# nrf52840_test_board.net
KiCad netlist of a schematic drawn in EasyEDA Pro
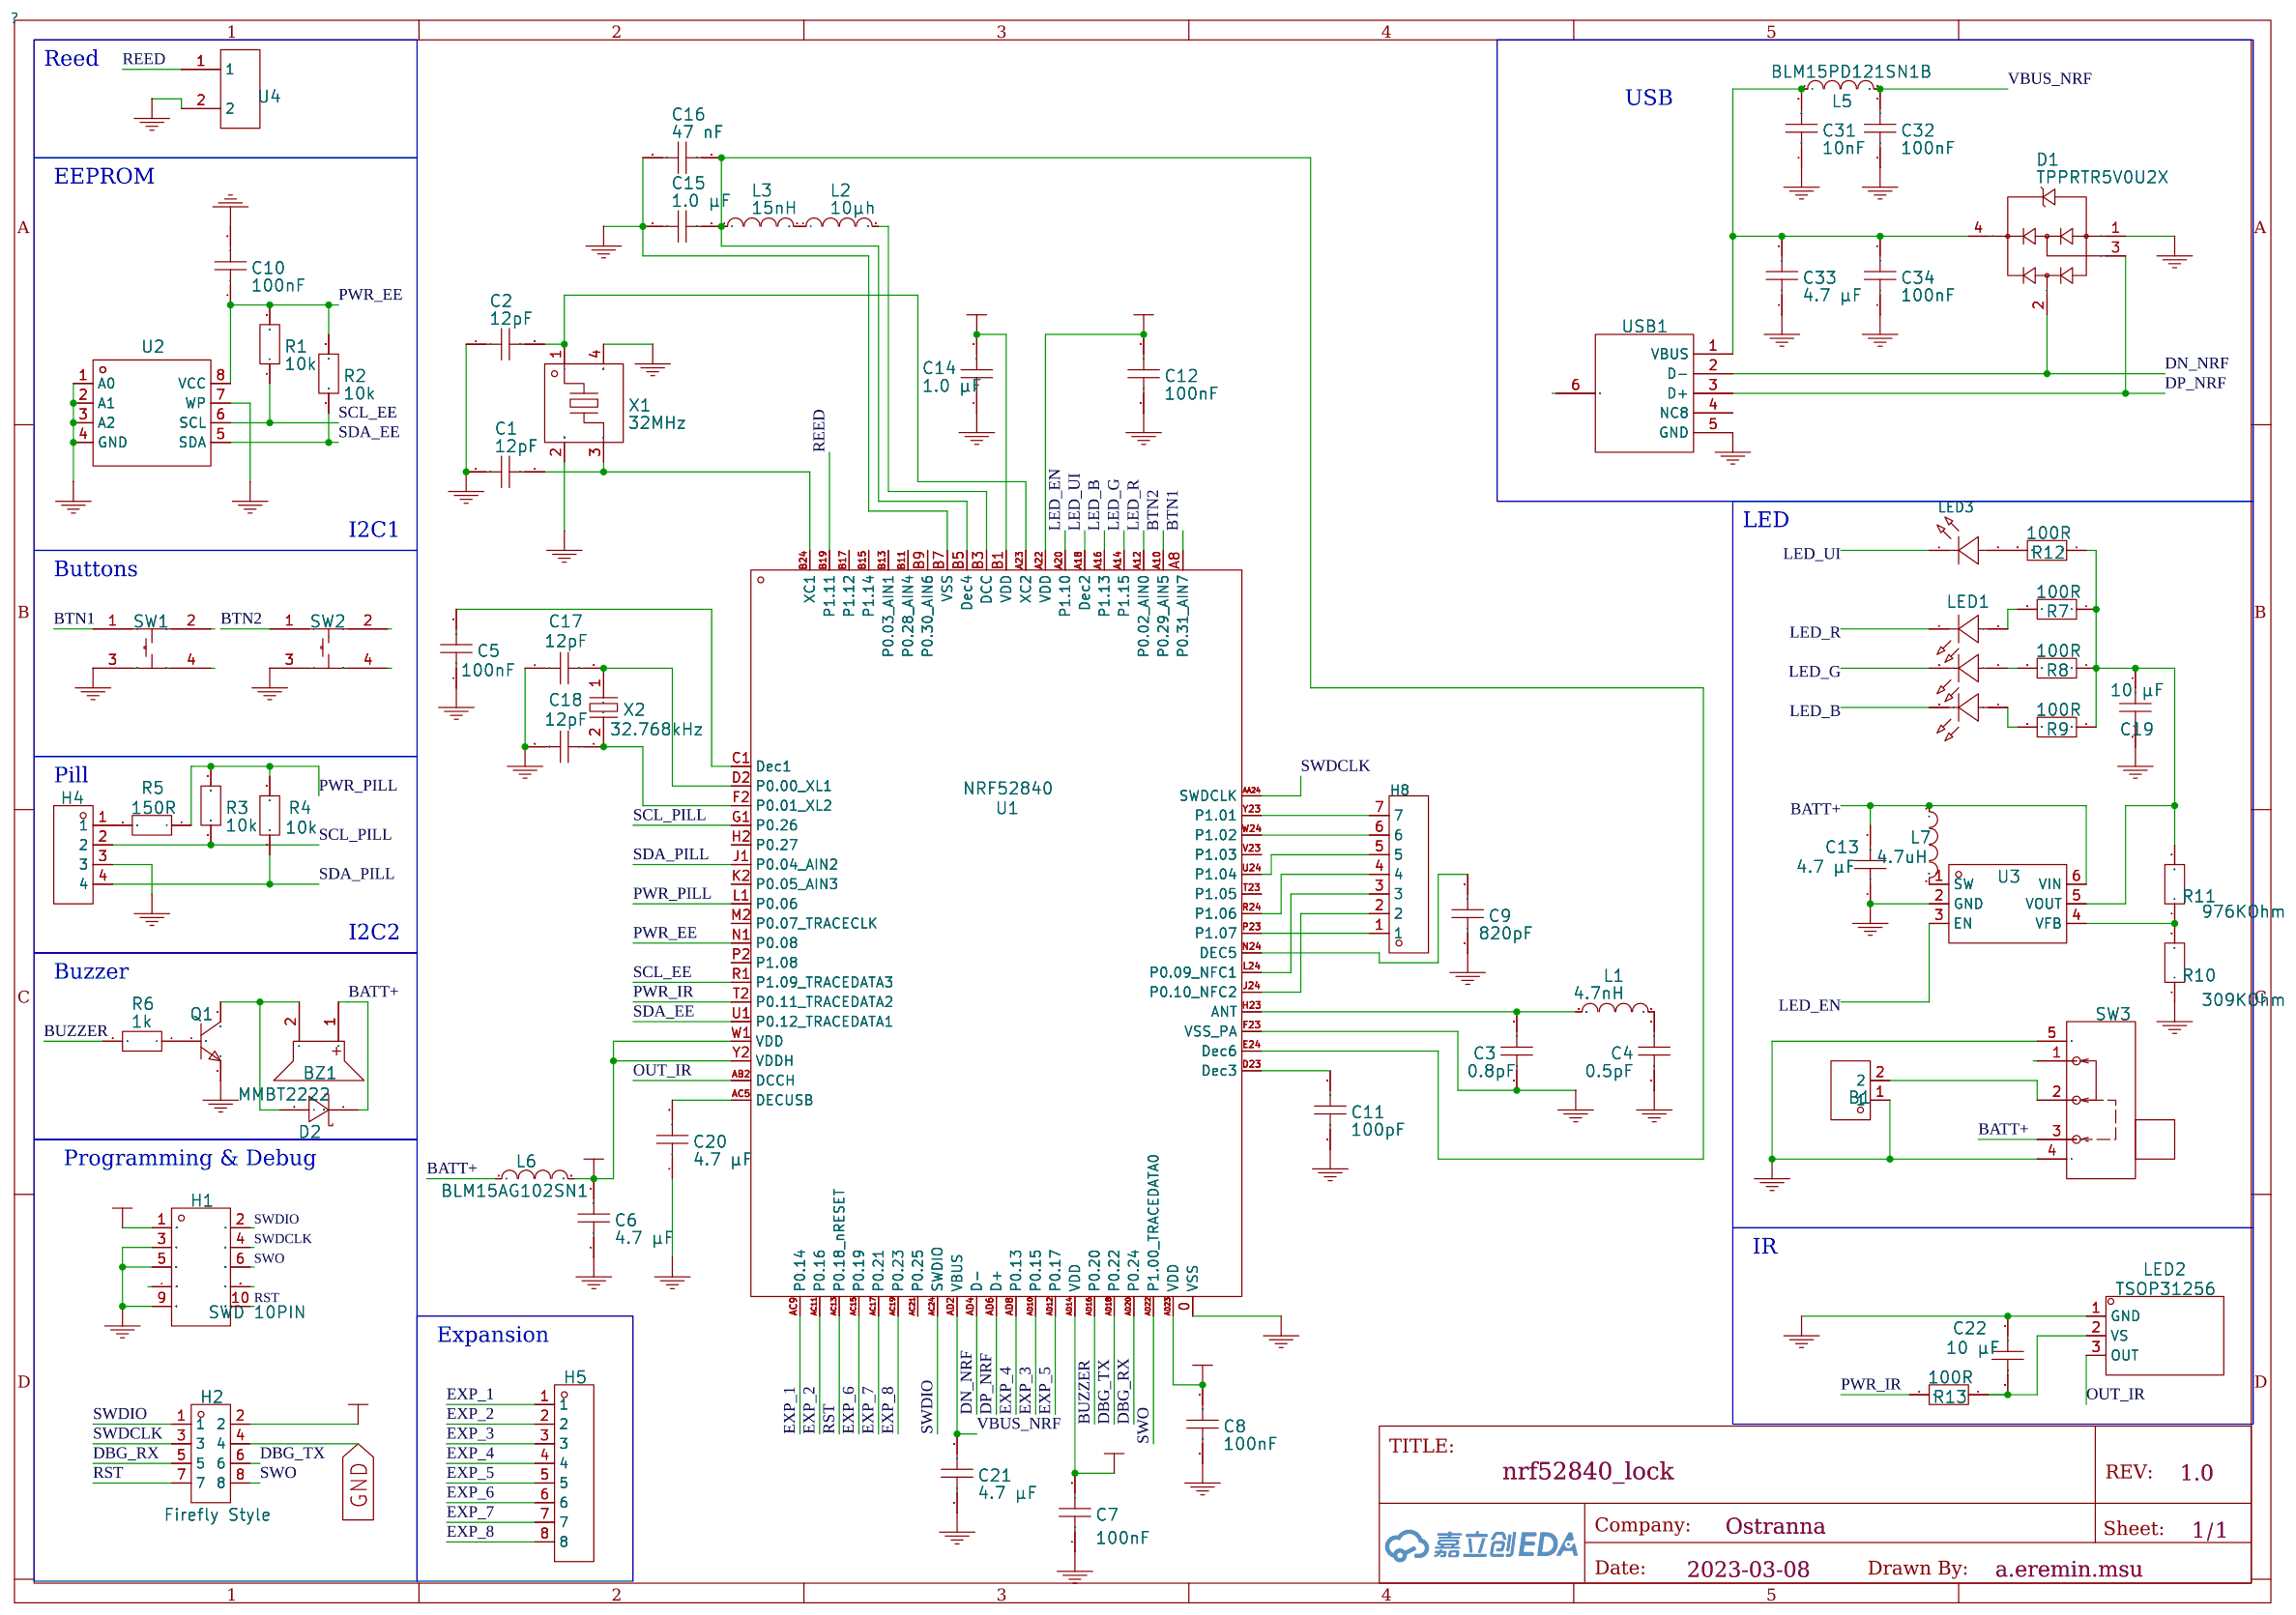
[diagram p0: schematic sheet]

(export (version "E")
  (design (tool "Eeschema 10.0.6"))
  (components
    (comp (ref "B1")
      (value "MF200V-11-02P")
      (footprint "easyedapro:HDR-TH_2P-P2.00-V-F-3")
      (fields (field (name "Manufacturer") "XFCN(兴飞)"))
      (libsource (lib "easyedapro") (part "MF200V-11-02P"))
    )
    (comp (ref "BZ1")
      (value "QMB-09B-03")
      (footprint "easyedapro:BUZ-TH_BD9.0-P4.00-D0.6-FD")
      (fields (field (name "Manufacturer") "华能"))
      (libsource (lib "easyedapro") (part "QMB-09B-03"))
    )
    (comp (ref "C1")
      (value "12pF")
      (footprint "easyedapro:C0402")
      (fields (field (name "Manufacturer Part") "0402CG120J500NT") (field (name "Manufacturer") "FH(风华)"))
      (libsource (lib "easyedapro") (part "12pF"))
    )
    (comp (ref "C2")
      (value "12pF")
      (footprint "easyedapro:C0402")
      (fields (field (name "Manufacturer Part") "0402CG120J500NT") (field (name "Manufacturer") "FH(风华)"))
      (libsource (lib "easyedapro") (part "12pF"))
    )
    (comp (ref "C3")
      (value "0.8pF")
      (footprint "easyedapro:C0402")
      (fields
        (field (name "Manufacturer Part") "GJM1555C1HR80WB01D")
        (field (name "Manufacturer") "muRata(村田)")
      )
      (libsource (lib "easyedapro") (part "0.8pF"))
    )
    (comp (ref "C4")
      (value "0.5pF")
      (footprint "easyedapro:C0402")
      (fields (field (name "Manufacturer Part") "0402CG0R5B500NT") (field (name "Manufacturer") "FH(风华)"))
      (libsource (lib "easyedapro") (part "0.5pF"))
    )
    (comp (ref "C5")
      (value "100nF")
      (footprint "easyedapro:C0402")
      (fields
        (field (name "Manufacturer Part") "GRM155R71C104KA88D")
        (field (name "Manufacturer") "muRata(村田)")
      )
      (libsource (lib "easyedapro") (part "100nF"))
    )
    (comp (ref "C6")
      (value "4.7 µF")
      (footprint "easyedapro:C0603")
      (fields
        (field (name "Manufacturer Part") "GRM188R60J475KE19D")
        (field (name "Manufacturer") "muRata(村田)")
      )
      (libsource (lib "easyedapro") (part "4.7 µF"))
    )
    (comp (ref "C7")
      (value "100nF")
      (footprint "easyedapro:C0402")
      (fields
        (field (name "Manufacturer Part") "GRM155R71C104KA88D")
        (field (name "Manufacturer") "muRata(村田)")
      )
      (libsource (lib "easyedapro") (part "100nF"))
    )
    (comp (ref "C8")
      (value "100nF")
      (footprint "easyedapro:C0402")
      (fields
        (field (name "Manufacturer Part") "GRM155R71C104KA88D")
        (field (name "Manufacturer") "muRata(村田)")
      )
      (libsource (lib "easyedapro") (part "100nF"))
    )
    (comp (ref "C9")
      (value "820pF")
      (footprint "easyedapro:C0402")
      (fields
        (field (name "Manufacturer Part") "GCM1555C1H821JA16D")
        (field (name "Manufacturer") "muRata(村田)")
      )
      (libsource (lib "easyedapro") (part "820pF"))
    )
    (comp (ref "C10")
      (value "100nF")
      (footprint "easyedapro:C0402")
      (fields
        (field (name "Manufacturer Part") "GRM155R71C104KA88D")
        (field (name "Manufacturer") "muRata(村田)")
      )
      (libsource (lib "easyedapro") (part "100nF"))
    )
    (comp (ref "C11")
      (value "100pF")
      (footprint "easyedapro:C0402")
      (fields
        (field (name "Manufacturer Part") "GCM1555C1H101JA16D")
        (field (name "Manufacturer") "muRata(村田)")
      )
      (libsource (lib "easyedapro") (part "100pF"))
    )
    (comp (ref "C12")
      (value "100nF")
      (footprint "easyedapro:C0402")
      (fields
        (field (name "Manufacturer Part") "GRM155R71C104KA88D")
        (field (name "Manufacturer") "muRata(村田)")
      )
      (libsource (lib "easyedapro") (part "100nF"))
    )
    (comp (ref "C13")
      (value "4.7 µF")
      (footprint "easyedapro:C0603")
      (fields
        (field (name "Manufacturer Part") "GRM188R60J475KE19D")
        (field (name "Manufacturer") "muRata(村田)")
      )
      (libsource (lib "easyedapro") (part "4.7 µF"))
    )
    (comp (ref "C14")
      (value "1.0 µF")
      (footprint "easyedapro:C0603")
      (fields
        (field (name "Manufacturer Part") "CL10A105KB8NNNC")
        (field (name "Manufacturer") "SAMSUNG(三星)")
      )
      (libsource (lib "easyedapro") (part "1.0 µF"))
    )
    (comp (ref "C15")
      (value "1.0 µF")
      (footprint "easyedapro:C0603")
      (fields
        (field (name "Manufacturer Part") "CL10A105KB8NNNC")
        (field (name "Manufacturer") "SAMSUNG(三星)")
      )
      (libsource (lib "easyedapro") (part "1.0 µF"))
    )
    (comp (ref "C16")
      (value "47 nF")
      (footprint "easyedapro:C0402")
      (fields (field (name "Manufacturer Part") "0402B473K250CT") (field (name "Manufacturer") "Walsin(华新科)"))
      (libsource (lib "easyedapro") (part "47 nF"))
    )
    (comp (ref "C17")
      (value "12pF")
      (footprint "easyedapro:C0402")
      (fields (field (name "Manufacturer Part") "0402CG120J500NT") (field (name "Manufacturer") "FH(风华)"))
      (libsource (lib "easyedapro") (part "12pF"))
    )
    (comp (ref "C18")
      (value "12pF")
      (footprint "easyedapro:C0402")
      (fields (field (name "Manufacturer Part") "0402CG120J500NT") (field (name "Manufacturer") "FH(风华)"))
      (libsource (lib "easyedapro") (part "12pF"))
    )
    (comp (ref "C19")
      (value "10 µF")
      (footprint "easyedapro:C0603")
      (fields
        (field (name "Manufacturer Part") "CL10A105KB8NNNC")
        (field (name "Manufacturer") "SAMSUNG(三星)")
      )
      (libsource (lib "easyedapro") (part "1.0 µF"))
    )
    (comp (ref "C20")
      (value "4.7 µF")
      (footprint "easyedapro:C0603")
      (fields
        (field (name "Manufacturer Part") "GRM188R60J475KE19D")
        (field (name "Manufacturer") "muRata(村田)")
      )
      (libsource (lib "easyedapro") (part "4.7 µF"))
    )
    (comp (ref "C21")
      (value "4.7 µF")
      (footprint "easyedapro:C0603")
      (fields
        (field (name "Manufacturer Part") "GRM188R60J475KE19D")
        (field (name "Manufacturer") "muRata(村田)")
      )
      (libsource (lib "easyedapro") (part "4.7 µF"))
    )
    (comp (ref "C22")
      (value "10 µF")
      (footprint "easyedapro:C0603")
      (fields
        (field (name "Manufacturer Part") "CL10A105KB8NNNC")
        (field (name "Manufacturer") "SAMSUNG(三星)")
      )
      (libsource (lib "easyedapro") (part "1.0 µF"))
    )
    (comp (ref "C31")
      (value "10nF")
      (footprint "easyedapro:C0402")
      (fields (field (name "Manufacturer Part") "0402B103J160NT") (field (name "Manufacturer") "FH(风华)"))
      (libsource (lib "easyedapro") (part "10nF"))
    )
    (comp (ref "C32")
      (value "100nF")
      (footprint "easyedapro:C0402")
      (fields
        (field (name "Manufacturer Part") "GRM155R71C104KA88D")
        (field (name "Manufacturer") "muRata(村田)")
      )
      (libsource (lib "easyedapro") (part "100nF"))
    )
    (comp (ref "C33")
      (value "4.7 µF")
      (footprint "easyedapro:C0603")
      (fields
        (field (name "Manufacturer Part") "GRM188R60J475KE19D")
        (field (name "Manufacturer") "muRata(村田)")
      )
      (libsource (lib "easyedapro") (part "4.7 µF"))
    )
    (comp (ref "C34")
      (value "100nF")
      (footprint "easyedapro:C0402")
      (fields
        (field (name "Manufacturer Part") "GRM155R71C104KA88D")
        (field (name "Manufacturer") "muRata(村田)")
      )
      (libsource (lib "easyedapro") (part "100nF"))
    )
    (comp (ref "D1")
      (value "TPPRTR5V0U2X")
      (footprint "easyedapro:SOT-143_L2.9-W1.3-P1.92-LS2.3-BR")
      (fields (field (name "Manufacturer") "TECH PUBLIC(台舟)"))
      (libsource (lib "easyedapro") (part "TPPRTR5V0U2X"))
    )
    (comp (ref "D2")
      (value "BAT54WS_C397611")
      (footprint "easyedapro:SOD-323_L1.8-W1.3-LS2.5-RD")
      (fields (field (name "Manufacturer Part") "BAT54WS") (field (name "Manufacturer") "AnBon(安邦)"))
      (libsource (lib "easyedapro") (part "BAT54WS_C397611"))
    )
    (comp (ref "H1")
      (value "SWD 10PIN")
      (footprint "easyedapro:HDR-SMD_10P-P1.27-V-M-R2-C5-LS5.5")
      (fields
        (field (name "Manufacturer Part") "KH-1.27PH180-2X5P-L7.2-SMT")
        (field (name "Manufacturer") "kinghelm(金航标)")
      )
      (libsource (lib "easyedapro") (part "SWD 10PIN"))
    )
    (comp (ref "H2")
      (value "Firefly Style")
      (footprint "easyedapro:HDR-TH_8P-P2.54-V-M-R2-C4-S2.54")
      (fields
        (field (name "Manufacturer Part") "DZ254R-22-08-63")
        (field (name "Manufacturer") "DEALON(德艺隆)")
      )
      (libsource (lib "easyedapro") (part "Firefly Style"))
    )
    (comp (ref "H4")
      (value "DW254W-11-04-85")
      (footprint "easyedapro:HDR-TH_4P-P2.54-H-F-W10.3-N")
      (fields (field (name "Manufacturer") "DEALON(德艺隆)"))
      (libsource (lib "easyedapro") (part "DW254W-11-04-85"))
    )
    (comp (ref "H5")
      (value "DW254W-11-08-85")
      (footprint "easyedapro:HDR-TH_8P-P2.54-H-F-W10.3-N")
      (fields (field (name "Manufacturer") "DEALON(德艺隆)"))
      (libsource (lib "easyedapro") (part "DW254W-11-08-85"))
    )
    (comp (ref "H8")
      (value "PZ254R-11-07P")
      (footprint "easyedapro:HDR-TH_7P-P2.54-H-M-W10.4")
      (fields (field (name "Manufacturer") "XFCN(兴飞)"))
      (libsource (lib "easyedapro") (part "PZ254R-11-07P"))
    )
    (comp (ref "L1")
      (value "4.7nH")
      (footprint "easyedapro:C0402")
      (fields (field (name "Manufacturer Part") "LQP15MN4N7B02D") (field (name "Manufacturer") "muRata(村田)"))
      (libsource (lib "easyedapro") (part "4.7nH"))
    )
    (comp (ref "L2")
      (value "10µh")
      (footprint "easyedapro:L0603")
      (fields
        (field (name "Manufacturer Part") "LBMF1608T100K")
        (field (name "Manufacturer") "TAIYO YUDEN(太诱)")
      )
      (libsource (lib "easyedapro") (part "10µh"))
    )
    (comp (ref "L3")
      (value "15nH")
      (footprint "easyedapro:C0402")
      (fields
        (field (name "Manufacturer Part") "CS0402-15NH-S")
        (field (name "Manufacturer") "chilisin(奇力新)")
      )
      (libsource (lib "easyedapro") (part "15nH"))
    )
    (comp (ref "L5")
      (value "BLM15PD121SN1B")
      (footprint "easyedapro:L0402")
      (fields (field (name "Manufacturer Part") "BLM15PD121SN1D") (field (name "Manufacturer") "muRata(村田)"))
      (libsource (lib "easyedapro") (part "BLM15PD121SN1B"))
    )
    (comp (ref "L6")
      (value "BLM15AG102SN1")
      (footprint "easyedapro:L0402")
      (fields (field (name "Manufacturer Part") "BLM15AG102SN1D") (field (name "Manufacturer") "muRata(村田)"))
      (libsource (lib "easyedapro") (part "BLM15AG102SN1"))
    )
    (comp (ref "L7")
      (value "4.7uH")
      (footprint "easyedapro:L0603")
      (fields
        (field (name "Manufacturer Part") "CPY160808T-4R7M-NP")
        (field (name "Manufacturer") "chilisin(奇力新)")
      )
      (libsource (lib "easyedapro") (part "4.7uH"))
    )
    (comp (ref "LED1")
      (value "TC5050RGBF08-3CJH-AF53A")
      (footprint "easyedapro:LED-SMD_6P-L5.0-W5.0-TL_TC5050RGBF08")
      (fields (field (name "Manufacturer") "TCWIN(天成)"))
      (libsource (lib "easyedapro") (part "TC5050RGBF08-3CJH-AF53A"))
    )
    (comp (ref "LED2")
      (value "TSOP31256")
      (footprint "easyedapro:SENSOR-TH_TSOP31256")
      (fields (field (name "Manufacturer") "VISHAY(威世)"))
      (libsource (lib "easyedapro") (part "TSOP31256"))
    )
    (comp (ref "LED3")
      (value "LTST-T680TGWT")
      (footprint "easyedapro:LED-SMD_L3.2-W2.8-LS3.5-RD_GREEN")
      (fields (field (name "Manufacturer") "LITEON(光宝)"))
      (libsource (lib "easyedapro") (part "LTST-T680TGWT"))
    )
    (comp (ref "Q1")
      (value "MMBT2222")
      (footprint "easyedapro:SOT-23-3_L2.9-W1.4-P1.91-LS2.6-BR")
      (fields (field (name "Manufacturer") "YONGYUTAI(永裕泰)"))
      (libsource (lib "easyedapro") (part "MMBT2222"))
    )
    (comp (ref "R1")
      (value "10k")
      (footprint "easyedapro:R0603")
      (fields
        (field (name "Manufacturer Part") "0603WAF1002T5E")
        (field (name "Manufacturer") "UNI-ROYAL(厚声)")
      )
      (libsource (lib "easyedapro") (part "10k"))
    )
    (comp (ref "R2")
      (value "10k")
      (footprint "easyedapro:R0603")
      (fields
        (field (name "Manufacturer Part") "0603WAF1002T5E")
        (field (name "Manufacturer") "UNI-ROYAL(厚声)")
      )
      (libsource (lib "easyedapro") (part "10k"))
    )
    (comp (ref "R3")
      (value "10k")
      (footprint "easyedapro:R0603")
      (fields
        (field (name "Manufacturer Part") "0603WAF1002T5E")
        (field (name "Manufacturer") "UNI-ROYAL(厚声)")
      )
      (libsource (lib "easyedapro") (part "10k"))
    )
    (comp (ref "R4")
      (value "10k")
      (footprint "easyedapro:R0603")
      (fields
        (field (name "Manufacturer Part") "0603WAF1002T5E")
        (field (name "Manufacturer") "UNI-ROYAL(厚声)")
      )
      (libsource (lib "easyedapro") (part "10k"))
    )
    (comp (ref "R5")
      (value "150R")
      (footprint "easyedapro:R0603")
      (fields
        (field (name "Manufacturer Part") "0603WAF1500T5E")
        (field (name "Manufacturer") "UNI-ROYAL(厚声)")
      )
      (libsource (lib "easyedapro") (part "150R"))
    )
    (comp (ref "R6")
      (value "1k")
      (footprint "easyedapro:R0603")
      (fields
        (field (name "Manufacturer Part") "0603WAF1001T5E")
        (field (name "Manufacturer") "UNI-ROYAL(厚声)")
      )
      (libsource (lib "easyedapro") (part "1k"))
    )
    (comp (ref "R7")
      (value "100R")
      (footprint "easyedapro:R0603")
      (fields
        (field (name "Manufacturer Part") "0603WAF1000T5E")
        (field (name "Manufacturer") "UNI-ROYAL(厚声)")
      )
      (libsource (lib "easyedapro") (part "100R"))
    )
    (comp (ref "R8")
      (value "100R")
      (footprint "easyedapro:R0603")
      (fields
        (field (name "Manufacturer Part") "0603WAF1000T5E")
        (field (name "Manufacturer") "UNI-ROYAL(厚声)")
      )
      (libsource (lib "easyedapro") (part "100R"))
    )
    (comp (ref "R9")
      (value "100R")
      (footprint "easyedapro:R0603")
      (fields
        (field (name "Manufacturer Part") "0603WAF1000T5E")
        (field (name "Manufacturer") "UNI-ROYAL(厚声)")
      )
      (libsource (lib "easyedapro") (part "100R"))
    )
    (comp (ref "R10")
      (value "309KOhm")
      (footprint "easyedapro:R0603")
      (fields
        (field (name "Manufacturer Part") "0603WAF3093T5E")
        (field (name "Manufacturer") "UNI-ROYAL(厚声)")
      )
      (libsource (lib "easyedapro") (part "309KOhm"))
    )
    (comp (ref "R11")
      (value "976KOhm")
      (footprint "easyedapro:R0603")
      (fields (field (name "Manufacturer Part") "RCT03976KFLF") (field (name "Manufacturer") "HKR"))
      (libsource (lib "easyedapro") (part "976KOhm"))
    )
    (comp (ref "R12")
      (value "100R")
      (footprint "easyedapro:R0603")
      (fields
        (field (name "Manufacturer Part") "0603WAF1000T5E")
        (field (name "Manufacturer") "UNI-ROYAL(厚声)")
      )
      (libsource (lib "easyedapro") (part "100R"))
    )
    (comp (ref "R13")
      (value "100R")
      (footprint "easyedapro:R0603")
      (fields
        (field (name "Manufacturer Part") "0603WAF1000T5E")
        (field (name "Manufacturer") "UNI-ROYAL(厚声)")
      )
      (libsource (lib "easyedapro") (part "100R"))
    )
    (comp (ref "SW1")
      (value "TS-1187A-C-D-B")
      (footprint "easyedapro:KEY-SMD_4P-L5.2-W5.2-P3.7-LS6.4-TL")
      (fields (field (name "Manufacturer") "XKB Connectivity(中国星坤)"))
      (libsource (lib "easyedapro") (part "TS-1187A-C-D-B"))
    )
    (comp (ref "SW2")
      (value "TS-1187A-C-D-B")
      (footprint "easyedapro:KEY-SMD_4P-L5.2-W5.2-P3.7-LS6.4-TL")
      (fields (field (name "Manufacturer") "XKB Connectivity(中国星坤)"))
      (libsource (lib "easyedapro") (part "TS-1187A-C-D-B"))
    )
    (comp (ref "SW3")
      (value "SS-12F44-G5_C2998807")
      (footprint "easyedapro:SW-TH_SS-12F44-G5_C2998807")
      (fields (field (name "Manufacturer Part") "SS-12F44-G5") (field (name "Manufacturer") "DEALON(德艺隆)"))
      (libsource (lib "easyedapro") (part "SS-12F44-G5_C2998807"))
    )
    (comp (ref "U1")
      (value "NRF52840")
      (footprint "easyedapro:AQFN-73_L7.0-W7.0-P0.50-BL-EP4.8-REDUCE-PAD")
      (fields (field (name "Manufacturer Part") "NRF52840-QIAA-R") (field (name "Manufacturer") "NORDIC"))
      (libsource (lib "easyedapro") (part "NRF52840"))
    )
    (comp (ref "U2")
      (value "BL24C256A-SFRC")
      (footprint "easyedapro:TSSOP-8_L4.4-W3.0-P0.65-LS6.4-BL")
      (fields (field (name "Manufacturer") "BL(上海贝岭)"))
      (libsource (lib "easyedapro") (part "BL24C256A-SFRC"))
    )
    (comp (ref "U3")
      (value "MCP1640CT-I/CHY")
      (footprint "easyedapro:SOT-23-6_L2.9-W1.6-P0.95-LS2.8-BR")
      (fields (field (name "Manufacturer") "MICROCHIP(美国微芯)"))
      (libsource (lib "easyedapro") (part "MCP1640CT-I/CHY"))
    )
    (comp (ref "U4")
      (value "59165-1-S-00-D")
      (footprint "easyedapro:SENSOR-SMD_59165-1-S-00-D")
      (fields (field (name "Manufacturer") "Littelfuse(美国力特)"))
      (libsource (lib "easyedapro") (part "59165-1-S-00-D"))
    )
    (comp (ref "USB1")
      (value "U254-051T-4BH83-S1S")
      (footprint "easyedapro:MICRO-USB-SMD_U254-051T-4BH83-S1S")
      (fields (field (name "Manufacturer") "XKB Connectivity(中国星坤)"))
      (libsource (lib "easyedapro") (part "U254-051T-4BH83-S1S"))
    )
    (comp (ref "X1")
      (value "32MHz")
      (footprint "easyedapro:CRYSTAL-SMD_4P-L2.0-W1.6-BL")
      (fields
        (field (name "Manufacturer Part") "SX1B32.000F0810F30")
        (field (name "Manufacturer") "SCTF(星通时频)")
      )
      (libsource (lib "easyedapro") (part "32MHz"))
    )
    (comp (ref "X2")
      (value "32.768kHz")
      (footprint "easyedapro:CRYSTAL-SMD_L3.2-W1.5")
      (fields (field (name "Manufacturer Part") "Q13FC13500005") (field (name "Manufacturer") "EPSON(爱普生)"))
      (libsource (lib "easyedapro") (part "32.768kHz"))
    )
  )
  (nets
    (net (code "1") (name "/BATT+") (class "Default")
      (node (ref "BZ1") (pin "1") (pinfunction "1_1") (pintype "input"))
      (node (ref "C13") (pin "2") (pinfunction "2_2") (pintype "input"))
      (node (ref "D2") (pin "1") (pinfunction "C_1") (pintype "input"))
      (node (ref "L6") (pin "1") (pinfunction "1_1") (pintype "input"))
      (node (ref "L7") (pin "1") (pinfunction "1_1") (pintype "input"))
      (node (ref "SW3") (pin "3") (pinfunction "3_3") (pintype "input"))
      (node (ref "U3") (pin "6") (pinfunction "VIN_6") (pintype "input"))
    )
    (net (code "2") (name "/BTN1") (class "Default")
      (node (ref "SW1") (pin "1") (pinfunction "1_1") (pintype "input"))
      (node (ref "U1") (pin "A8") (pinfunction "P0.31_AIN7_A8") (pintype "bidirectional"))
    )
    (net (code "3") (name "/BTN2") (class "Default")
      (node (ref "SW2") (pin "1") (pinfunction "1_1") (pintype "input"))
      (node (ref "U1") (pin "A10") (pinfunction "P0.29_AIN5_A10") (pintype "bidirectional"))
    )
    (net (code "4") (name "/BUZZER") (class "Default")
      (node (ref "R6") (pin "2") (pinfunction "2_2") (pintype "input"))
      (node (ref "U1") (pin "AD16") (pinfunction "P0.20_AD16") (pintype "bidirectional"))
    )
    (net (code "5") (name "/DBG_RX") (class "Default")
      (node (ref "H2") (pin "5") (pinfunction "5_5") (pintype "input"))
      (node (ref "U1") (pin "AD20") (pinfunction "P0.24_AD20") (pintype "bidirectional"))
    )
    (net (code "6") (name "/DBG_TX") (class "Default")
      (node (ref "H2") (pin "6") (pinfunction "6_6") (pintype "input"))
      (node (ref "U1") (pin "AD18") (pinfunction "P0.22_AD18") (pintype "bidirectional"))
    )
    (net (code "7") (name "/DN_NRF") (class "Default")
      (node (ref "D1") (pin "2") (pinfunction "2_2") (pintype "input"))
      (node (ref "U1") (pin "AD4") (pinfunction "D-_AD4") (pintype "input"))
      (node (ref "USB1") (pin "2") (pinfunction "D-_2") (pintype "input"))
    )
    (net (code "8") (name "/DP_NRF") (class "Default")
      (node (ref "D1") (pin "3") (pinfunction "3_3") (pintype "input"))
      (node (ref "U1") (pin "AD6") (pinfunction "D+_AD6") (pintype "input"))
      (node (ref "USB1") (pin "3") (pinfunction "D+_3") (pintype "input"))
    )
    (net (code "9") (name "/EXP_1") (class "Default")
      (node (ref "H5") (pin "1") (pinfunction "1_1") (pintype "input"))
      (node (ref "U1") (pin "AC9") (pinfunction "P0.14_AC9") (pintype "bidirectional"))
    )
    (net (code "10") (name "/EXP_2") (class "Default")
      (node (ref "H5") (pin "2") (pinfunction "2_2") (pintype "input"))
      (node (ref "U1") (pin "AC11") (pinfunction "P0.16_AC11") (pintype "bidirectional"))
    )
    (net (code "11") (name "/EXP_3") (class "Default")
      (node (ref "H5") (pin "3") (pinfunction "3_3") (pintype "input"))
      (node (ref "U1") (pin "AD10") (pinfunction "P0.15_AD10") (pintype "bidirectional"))
    )
    (net (code "12") (name "/EXP_4") (class "Default")
      (node (ref "H5") (pin "4") (pinfunction "4_4") (pintype "input"))
      (node (ref "U1") (pin "AD8") (pinfunction "P0.13_AD8") (pintype "bidirectional"))
    )
    (net (code "13") (name "/EXP_5") (class "Default")
      (node (ref "H5") (pin "5") (pinfunction "5_5") (pintype "input"))
      (node (ref "U1") (pin "AD12") (pinfunction "P0.17_AD12") (pintype "bidirectional"))
    )
    (net (code "14") (name "/EXP_6") (class "Default")
      (node (ref "H5") (pin "6") (pinfunction "6_6") (pintype "input"))
      (node (ref "U1") (pin "AC15") (pinfunction "P0.19_AC15") (pintype "bidirectional"))
    )
    (net (code "15") (name "/EXP_7") (class "Default")
      (node (ref "H5") (pin "7") (pinfunction "7_7") (pintype "input"))
      (node (ref "U1") (pin "AC17") (pinfunction "P0.21_AC17") (pintype "bidirectional"))
    )
    (net (code "16") (name "/EXP_8") (class "Default")
      (node (ref "H5") (pin "8") (pinfunction "8_8") (pintype "input"))
      (node (ref "U1") (pin "AC19") (pinfunction "P0.23_AC19") (pintype "bidirectional"))
    )
    (net (code "17") (name "/LED_B") (class "Default")
      (node (ref "LED1") (pin "6") (pinfunction "-_6") (pintype "input"))
      (node (ref "U1") (pin "A16") (pinfunction "P1.13_A16") (pintype "bidirectional"))
    )
    (net (code "18") (name "/LED_EN") (class "Default")
      (node (ref "U1") (pin "A20") (pinfunction "P1.10_A20") (pintype "bidirectional"))
      (node (ref "U3") (pin "3") (pinfunction "EN_3") (pintype "input"))
    )
    (net (code "19") (name "/LED_G") (class "Default")
      (node (ref "LED1") (pin "5") (pinfunction "-_5") (pintype "input"))
      (node (ref "U1") (pin "A14") (pinfunction "P1.15_A14") (pintype "bidirectional"))
    )
    (net (code "20") (name "/LED_R") (class "Default")
      (node (ref "LED1") (pin "4") (pinfunction "-_4") (pintype "input"))
      (node (ref "U1") (pin "A12") (pinfunction "P0.02_AIN0_A12") (pintype "bidirectional"))
    )
    (net (code "21") (name "/LED_UI") (class "Default")
      (node (ref "LED3") (pin "1") (pinfunction "-_1") (pintype "input"))
      (node (ref "U1") (pin "A18") (pinfunction "Dec2_A18") (pintype "input"))
    )
    (net (code "22") (name "/OUT_IR") (class "Default")
      (node (ref "LED2") (pin "3") (pinfunction "OUT_3") (pintype "input"))
      (node (ref "U1") (pin "AB2") (pinfunction "DCCH_AB2") (pintype "input"))
    )
    (net (code "23") (name "/PWR_EE") (class "Default")
      (node (ref "C10") (pin "1") (pinfunction "1_1") (pintype "input"))
      (node (ref "R1") (pin "2") (pinfunction "2_2") (pintype "input"))
      (node (ref "R2") (pin "2") (pinfunction "2_2") (pintype "input"))
      (node (ref "U1") (pin "N1") (pinfunction "P0.08_N1") (pintype "bidirectional"))
      (node (ref "U2") (pin "8") (pinfunction "VCC_8") (pintype "input"))
    )
    (net (code "24") (name "/PWR_IR") (class "Default")
      (node (ref "R13") (pin "2") (pinfunction "2_2") (pintype "input"))
      (node (ref "U1") (pin "T2") (pinfunction "P0.11_TRACEDATA2_T2") (pintype "bidirectional"))
    )
    (net (code "25") (name "/PWR_PILL") (class "Default")
      (node (ref "R3") (pin "2") (pinfunction "2_2") (pintype "input"))
      (node (ref "R4") (pin "2") (pinfunction "2_2") (pintype "input"))
      (node (ref "R5") (pin "1") (pinfunction "1_1") (pintype "input"))
      (node (ref "U1") (pin "L1") (pinfunction "P0.06_L1") (pintype "bidirectional"))
    )
    (net (code "26") (name "/REED") (class "Default")
      (node (ref "U1") (pin "B19") (pinfunction "P1.11_B19") (pintype "bidirectional"))
      (node (ref "U4") (pin "1") (pinfunction "1_1") (pintype "input"))
    )
    (net (code "27") (name "/RST") (class "Default")
      (node (ref "H1") (pin "10") (pinfunction "RST_10") (pintype "input"))
      (node (ref "H2") (pin "7") (pinfunction "7_7") (pintype "input"))
      (node (ref "U1") (pin "AC13") (pinfunction "P0.18_nRESET_AC13") (pintype "bidirectional"))
    )
    (net (code "28") (name "/SCL_EE") (class "Default")
      (node (ref "R1") (pin "1") (pinfunction "1_1") (pintype "input"))
      (node (ref "U1") (pin "R1") (pinfunction "P1.09_TRACEDATA3_R1") (pintype "bidirectional"))
      (node (ref "U2") (pin "6") (pinfunction "SCL_6") (pintype "input"))
    )
    (net (code "29") (name "/SCL_PILL") (class "Default")
      (node (ref "H4") (pin "2") (pinfunction "2_2") (pintype "input"))
      (node (ref "R3") (pin "1") (pinfunction "1_1") (pintype "input"))
      (node (ref "U1") (pin "G1") (pinfunction "P0.26_G1") (pintype "bidirectional"))
    )
    (net (code "30") (name "/SDA_EE") (class "Default")
      (node (ref "R2") (pin "1") (pinfunction "1_1") (pintype "input"))
      (node (ref "U1") (pin "U1") (pinfunction "P0.12_TRACEDATA1_U1") (pintype "bidirectional"))
      (node (ref "U2") (pin "5") (pinfunction "SDA_5") (pintype "input"))
    )
    (net (code "31") (name "/SDA_PILL") (class "Default")
      (node (ref "H4") (pin "4") (pinfunction "4_4") (pintype "input"))
      (node (ref "R4") (pin "1") (pinfunction "1_1") (pintype "input"))
      (node (ref "U1") (pin "J1") (pinfunction "P0.04_AIN2_J1") (pintype "bidirectional"))
    )
    (net (code "32") (name "/SWDCLK") (class "Default")
      (node (ref "H1") (pin "4") (pinfunction "CLK_4") (pintype "input"))
      (node (ref "H2") (pin "3") (pinfunction "3_3") (pintype "input"))
      (node (ref "U1") (pin "AA24") (pinfunction "SWDCLK_AA24") (pintype "input"))
    )
    (net (code "33") (name "/SWDIO") (class "Default")
      (node (ref "H1") (pin "2") (pinfunction "IO_2") (pintype "input"))
      (node (ref "H2") (pin "1") (pinfunction "1_1") (pintype "input"))
      (node (ref "U1") (pin "AC24") (pinfunction "SWDIO_AC24") (pintype "input"))
    )
    (net (code "34") (name "/SWO") (class "Default")
      (node (ref "H1") (pin "6") (pinfunction "SWO_6") (pintype "input"))
      (node (ref "H2") (pin "8") (pinfunction "8_8") (pintype "input"))
      (node (ref "U1") (pin "AD22") (pinfunction "P1.00_TRACEDATA0_AD22") (pintype "input"))
    )
    (net (code "35") (name "/VBUS_NRF") (class "Default")
      (node (ref "C21") (pin "2") (pinfunction "2_2") (pintype "input"))
      (node (ref "C32") (pin "2") (pinfunction "2_2") (pintype "input"))
      (node (ref "L5") (pin "2") (pinfunction "2_2") (pintype "input"))
      (node (ref "U1") (pin "AD2") (pinfunction "VBUS_AD2") (pintype "input"))
    )
    (net (code "36") (name "GND") (class "Default")
      (node (ref "B1") (pin "1") (pinfunction "1_1") (pintype "input"))
      (node (ref "C1") (pin "2") (pinfunction "2_2") (pintype "input"))
      (node (ref "C10") (pin "2") (pinfunction "2_2") (pintype "input"))
      (node (ref "C11") (pin "1") (pinfunction "1_1") (pintype "input"))
      (node (ref "C12") (pin "1") (pinfunction "1_1") (pintype "input"))
      (node (ref "C13") (pin "1") (pinfunction "1_1") (pintype "input"))
      (node (ref "C14") (pin "1") (pinfunction "1_1") (pintype "input"))
      (node (ref "C15") (pin "2") (pinfunction "2_2") (pintype "input"))
      (node (ref "C16") (pin "2") (pinfunction "2_2") (pintype "input"))
      (node (ref "C17") (pin "1") (pinfunction "1_1") (pintype "input"))
      (node (ref "C18") (pin "2") (pinfunction "2_2") (pintype "input"))
      (node (ref "C19") (pin "2") (pinfunction "2_2") (pintype "input"))
      (node (ref "C2") (pin "1") (pinfunction "1_1") (pintype "input"))
      (node (ref "C20") (pin "1") (pinfunction "1_1") (pintype "input"))
      (node (ref "C21") (pin "1") (pinfunction "1_1") (pintype "input"))
      (node (ref "C22") (pin "1") (pinfunction "1_1") (pintype "input"))
      (node (ref "C3") (pin "2") (pinfunction "2_2") (pintype "input"))
      (node (ref "C31") (pin "1") (pinfunction "1_1") (pintype "input"))
      (node (ref "C32") (pin "1") (pinfunction "1_1") (pintype "input"))
      (node (ref "C33") (pin "1") (pinfunction "1_1") (pintype "input"))
      (node (ref "C34") (pin "1") (pinfunction "1_1") (pintype "input"))
      (node (ref "C4") (pin "2") (pinfunction "2_2") (pintype "input"))
      (node (ref "C5") (pin "1") (pinfunction "1_1") (pintype "input"))
      (node (ref "C6") (pin "1") (pinfunction "1_1") (pintype "input"))
      (node (ref "C7") (pin "1") (pinfunction "1_1") (pintype "input"))
      (node (ref "C8") (pin "1") (pinfunction "1_1") (pintype "input"))
      (node (ref "C9") (pin "1") (pinfunction "1_1") (pintype "input"))
      (node (ref "D1") (pin "1") (pinfunction "1_1") (pintype "input"))
      (node (ref "H1") (pin "3") (pinfunction "0_3") (pintype "input"))
      (node (ref "H1") (pin "5") (pinfunction "0_5") (pintype "input"))
      (node (ref "H1") (pin "9") (pinfunction "0_9") (pintype "input"))
      (node (ref "H2") (pin "4") (pinfunction "4_4") (pintype "input"))
      (node (ref "H4") (pin "3") (pinfunction "3_3") (pintype "input"))
      (node (ref "LED2") (pin "1") (pinfunction "GND_1") (pintype "input"))
      (node (ref "Q1") (pin "2") (pinfunction "E_2") (pintype "input"))
      (node (ref "R10") (pin "1") (pinfunction "1_1") (pintype "input"))
      (node (ref "SW1") (pin "3") (pinfunction "3_3") (pintype "input"))
      (node (ref "SW2") (pin "3") (pinfunction "3_3") (pintype "input"))
      (node (ref "SW3") (pin "4") (pinfunction "4_4") (pintype "input"))
      (node (ref "SW3") (pin "5") (pinfunction "5_5") (pintype "input"))
      (node (ref "U1") (pin "0") (pinfunction "VSS_0") (pintype "input"))
      (node (ref "U1") (pin "B7") (pinfunction "VSS_B7") (pintype "input"))
      (node (ref "U1") (pin "F23") (pinfunction "VSS_PA_F23") (pintype "input"))
      (node (ref "U2") (pin "1") (pinfunction "A0_1") (pintype "input"))
      (node (ref "U2") (pin "2") (pinfunction "A1_2") (pintype "input"))
      (node (ref "U2") (pin "3") (pinfunction "A2_3") (pintype "input"))
      (node (ref "U2") (pin "4") (pinfunction "GND_4") (pintype "input"))
      (node (ref "U2") (pin "7") (pinfunction "WP_7") (pintype "input"))
      (node (ref "U3") (pin "2") (pinfunction "GND_2") (pintype "input"))
      (node (ref "U4") (pin "2") (pinfunction "2_2") (pintype "input"))
      (node (ref "USB1") (pin "5") (pinfunction "GND_5") (pintype "input"))
      (node (ref "X1") (pin "2") (pinfunction "GND_2") (pintype "input"))
      (node (ref "X1") (pin "4") (pinfunction "GND_4") (pintype "input"))
    )
    (net (code "37") (name "Net-(B1-Pad2)") (class "Default")
      (node (ref "B1") (pin "2") (pinfunction "2_2") (pintype "input"))
      (node (ref "SW3") (pin "2") (pinfunction "2_2") (pintype "input"))
    )
    (net (code "38") (name "Net-(C4-Pad1)") (class "Default")
      (node (ref "C4") (pin "1") (pinfunction "1_1") (pintype "input"))
      (node (ref "L1") (pin "1") (pinfunction "1_1") (pintype "input"))
    )
    (net (code "39") (name "Net-(D2-A)") (class "Default")
      (node (ref "BZ1") (pin "2") (pinfunction "2_2") (pintype "input"))
      (node (ref "D2") (pin "2") (pinfunction "A_2") (pintype "input"))
      (node (ref "Q1") (pin "3") (pinfunction "C_3") (pintype "input"))
    )
    (net (code "40") (name "Net-(H4-Pad1)") (class "Default")
      (node (ref "H4") (pin "1") (pinfunction "1_1") (pintype "input"))
      (node (ref "R5") (pin "2") (pinfunction "2_2") (pintype "input"))
    )
    (net (code "41") (name "Net-(L2-Pad1)") (class "Default")
      (node (ref "L2") (pin "1") (pinfunction "1_1") (pintype "input"))
      (node (ref "L3") (pin "2") (pinfunction "2_2") (pintype "input"))
    )
    (net (code "42") (name "Net-(LED1-+-Pad1)") (class "Default")
      (node (ref "LED1") (pin "1") (pinfunction "+_1") (pintype "input"))
      (node (ref "R9") (pin "2") (pinfunction "2_2") (pintype "input"))
    )
    (net (code "43") (name "Net-(LED1-+-Pad2)") (class "Default")
      (node (ref "LED1") (pin "2") (pinfunction "+_2") (pintype "input"))
      (node (ref "R8") (pin "2") (pinfunction "2_2") (pintype "input"))
    )
    (net (code "44") (name "Net-(LED1-+-Pad3)") (class "Default")
      (node (ref "LED1") (pin "3") (pinfunction "+_3") (pintype "input"))
      (node (ref "R7") (pin "2") (pinfunction "2_2") (pintype "input"))
    )
    (net (code "45") (name "Net-(LED2-VS)") (class "Default")
      (node (ref "C22") (pin "2") (pinfunction "2_2") (pintype "input"))
      (node (ref "LED2") (pin "2") (pinfunction "VS_2") (pintype "input"))
      (node (ref "R13") (pin "1") (pinfunction "1_1") (pintype "input"))
    )
    (net (code "46") (name "Net-(LED3-+)") (class "Default")
      (node (ref "LED3") (pin "2") (pinfunction "+_2") (pintype "input"))
      (node (ref "R12") (pin "2") (pinfunction "2_2") (pintype "input"))
    )
    (net (code "47") (name "Net-(Q1-B)") (class "Default")
      (node (ref "Q1") (pin "1") (pinfunction "B_1") (pintype "input"))
      (node (ref "R6") (pin "1") (pinfunction "1_1") (pintype "input"))
    )
    (net (code "48") (name "Net-(U1-ANT)") (class "Default")
      (node (ref "C3") (pin "1") (pinfunction "1_1") (pintype "input"))
      (node (ref "L1") (pin "2") (pinfunction "2_2") (pintype "input"))
      (node (ref "U1") (pin "H23") (pinfunction "ANT_H23") (pintype "input"))
    )
    (net (code "49") (name "Net-(U1-DCC)") (class "Default")
      (node (ref "L2") (pin "2") (pinfunction "2_2") (pintype "input"))
      (node (ref "U1") (pin "B3") (pinfunction "DCC_B3") (pintype "input"))
    )
    (net (code "50") (name "Net-(U1-DEC5)") (class "Default")
      (node (ref "C9") (pin "2") (pinfunction "2_2") (pintype "input"))
      (node (ref "U1") (pin "N24") (pinfunction "DEC5_N24") (pintype "input"))
    )
    (net (code "51") (name "Net-(U1-DECUSB)") (class "Default")
      (node (ref "C20") (pin "2") (pinfunction "2_2") (pintype "input"))
      (node (ref "U1") (pin "AC5") (pinfunction "DECUSB_AC5") (pintype "input"))
    )
    (net (code "52") (name "Net-(U1-Dec1)") (class "Default")
      (node (ref "C5") (pin "2") (pinfunction "2_2") (pintype "input"))
      (node (ref "U1") (pin "C1") (pinfunction "Dec1_C1") (pintype "input"))
    )
    (net (code "53") (name "Net-(U1-Dec3)") (class "Default")
      (node (ref "C11") (pin "2") (pinfunction "2_2") (pintype "input"))
      (node (ref "U1") (pin "D23") (pinfunction "Dec3_D23") (pintype "input"))
    )
    (net (code "54") (name "Net-(U1-Dec4)") (class "Default")
      (node (ref "C15") (pin "1") (pinfunction "1_1") (pintype "input"))
      (node (ref "C16") (pin "1") (pinfunction "1_1") (pintype "input"))
      (node (ref "L3") (pin "1") (pinfunction "1_1") (pintype "input"))
      (node (ref "U1") (pin "B5") (pinfunction "Dec4_B5") (pintype "input"))
      (node (ref "U1") (pin "E24") (pinfunction "Dec6_E24") (pintype "input"))
    )
    (net (code "55") (name "Net-(U1-P0.00_XL1)") (class "Default")
      (node (ref "C17") (pin "2") (pinfunction "2_2") (pintype "input"))
      (node (ref "U1") (pin "D2") (pinfunction "P0.00_XL1_D2") (pintype "bidirectional"))
      (node (ref "X2") (pin "1") (pinfunction "1_1") (pintype "input"))
    )
    (net (code "56") (name "Net-(U1-P0.01_XL2)") (class "Default")
      (node (ref "C18") (pin "1") (pinfunction "1_1") (pintype "input"))
      (node (ref "U1") (pin "F2") (pinfunction "P0.01_XL2_F2") (pintype "bidirectional"))
      (node (ref "X2") (pin "2") (pinfunction "GND_2") (pintype "input"))
    )
    (net (code "57") (name "Net-(U1-P0.09_NFC1)") (class "Default")
      (node (ref "H8") (pin "3") (pinfunction "3_3") (pintype "input"))
      (node (ref "U1") (pin "L24") (pinfunction "P0.09_NFC1_L24") (pintype "input"))
    )
    (net (code "58") (name "Net-(U1-P0.10_NFC2)") (class "Default")
      (node (ref "H8") (pin "2") (pinfunction "2_2") (pintype "input"))
      (node (ref "U1") (pin "J24") (pinfunction "P0.10_NFC2_J24") (pintype "input"))
    )
    (net (code "59") (name "Net-(U1-P1.01)") (class "Default")
      (node (ref "H8") (pin "7") (pinfunction "7_7") (pintype "input"))
      (node (ref "U1") (pin "Y23") (pinfunction "P1.01_Y23") (pintype "bidirectional"))
    )
    (net (code "60") (name "Net-(U1-P1.02)") (class "Default")
      (node (ref "H8") (pin "6") (pinfunction "6_6") (pintype "input"))
      (node (ref "U1") (pin "W24") (pinfunction "P1.02_W24") (pintype "bidirectional"))
    )
    (net (code "61") (name "Net-(U1-P1.04)") (class "Default")
      (node (ref "H8") (pin "5") (pinfunction "5_5") (pintype "input"))
      (node (ref "U1") (pin "U24") (pinfunction "P1.04_U24") (pintype "bidirectional"))
    )
    (net (code "62") (name "Net-(U1-P1.06)") (class "Default")
      (node (ref "H8") (pin "4") (pinfunction "4_4") (pintype "input"))
      (node (ref "U1") (pin "R24") (pinfunction "P1.06_R24") (pintype "bidirectional"))
    )
    (net (code "63") (name "Net-(U1-P1.07)") (class "Default")
      (node (ref "H8") (pin "1") (pinfunction "1_1") (pintype "input"))
      (node (ref "U1") (pin "P23") (pinfunction "P1.07_P23") (pintype "bidirectional"))
    )
    (net (code "64") (name "Net-(U1-XC1)") (class "Default")
      (node (ref "C1") (pin "1") (pinfunction "1_1") (pintype "input"))
      (node (ref "U1") (pin "B24") (pinfunction "XC1_B24") (pintype "input"))
      (node (ref "X1") (pin "3") (pinfunction "3_3") (pintype "input"))
    )
    (net (code "65") (name "Net-(U1-XC2)") (class "Default")
      (node (ref "C2") (pin "2") (pinfunction "2_2") (pintype "input"))
      (node (ref "U1") (pin "A23") (pinfunction "XC2_A23") (pintype "input"))
      (node (ref "X1") (pin "1") (pinfunction "1_1") (pintype "input"))
    )
    (net (code "66") (name "Net-(U3-SW)") (class "Default")
      (node (ref "L7") (pin "2") (pinfunction "2_2") (pintype "input"))
      (node (ref "U3") (pin "1") (pinfunction "SW_1") (pintype "input"))
    )
    (net (code "67") (name "Net-(U3-VFB)") (class "Default")
      (node (ref "R10") (pin "2") (pinfunction "2_2") (pintype "input"))
      (node (ref "R11") (pin "1") (pinfunction "1_1") (pintype "input"))
      (node (ref "U3") (pin "4") (pinfunction "VFB_4") (pintype "input"))
    )
    (net (code "68") (name "Net-(U3-VOUT)") (class "Default")
      (node (ref "C19") (pin "1") (pinfunction "1_1") (pintype "input"))
      (node (ref "R11") (pin "2") (pinfunction "2_2") (pintype "input"))
      (node (ref "R12") (pin "1") (pinfunction "1_1") (pintype "input"))
      (node (ref "R7") (pin "1") (pinfunction "1_1") (pintype "input"))
      (node (ref "R8") (pin "1") (pinfunction "1_1") (pintype "input"))
      (node (ref "R9") (pin "1") (pinfunction "1_1") (pintype "input"))
      (node (ref "U3") (pin "5") (pinfunction "VOUT_5") (pintype "input"))
    )
    (net (code "69") (name "Net-(USB1-VBUS)") (class "Default")
      (node (ref "C31") (pin "2") (pinfunction "2_2") (pintype "input"))
      (node (ref "C33") (pin "2") (pinfunction "2_2") (pintype "input"))
      (node (ref "C34") (pin "2") (pinfunction "2_2") (pintype "input"))
      (node (ref "D1") (pin "4") (pinfunction "4_4") (pintype "input"))
      (node (ref "L5") (pin "1") (pinfunction "1_1") (pintype "input"))
      (node (ref "USB1") (pin "1") (pinfunction "VBUS_1") (pintype "input"))
    )
    (net (code "70") (name "VCC") (class "Default")
      (node (ref "C12") (pin "2") (pinfunction "2_2") (pintype "input"))
      (node (ref "C14") (pin "2") (pinfunction "2_2") (pintype "input"))
      (node (ref "C6") (pin "2") (pinfunction "2_2") (pintype "input"))
      (node (ref "C7") (pin "2") (pinfunction "2_2") (pintype "input"))
      (node (ref "C8") (pin "2") (pinfunction "2_2") (pintype "input"))
      (node (ref "H1") (pin "1") (pinfunction "VCC_1") (pintype "input"))
      (node (ref "H2") (pin "2") (pinfunction "2_2") (pintype "input"))
      (node (ref "L6") (pin "2") (pinfunction "2_2") (pintype "input"))
      (node (ref "U1") (pin "A22") (pinfunction "VDD_A22") (pintype "input"))
      (node (ref "U1") (pin "AD14") (pinfunction "VDD_AD14") (pintype "input"))
      (node (ref "U1") (pin "AD23") (pinfunction "VDD_AD23") (pintype "input"))
      (node (ref "U1") (pin "B1") (pinfunction "VDD_B1") (pintype "input"))
      (node (ref "U1") (pin "W1") (pinfunction "VDD_W1") (pintype "input"))
      (node (ref "U1") (pin "Y2") (pinfunction "VDDH_Y2") (pintype "input"))
    )
    (net (code "71") (name "unconnected-(H1-NC1-Pad8)") (class "Default")
      (node (ref "H1") (pin "8") (pinfunction "NC1_8") (pintype "input"))
    )
    (net (code "72") (name "unconnected-(H1-NC2-Pad7)") (class "Default")
      (node (ref "H1") (pin "7") (pinfunction "NC2_7") (pintype "input"))
    )
    (net (code "73") (name "unconnected-(SW1-NC3-Pad2)") (class "Default")
      (node (ref "SW1") (pin "2") (pinfunction "NC3_2") (pintype "input"))
    )
    (net (code "74") (name "unconnected-(SW1-NC4-Pad4)") (class "Default")
      (node (ref "SW1") (pin "4") (pinfunction "NC4_4") (pintype "input"))
    )
    (net (code "75") (name "unconnected-(SW2-NC3-Pad2)") (class "Default")
      (node (ref "SW2") (pin "2") (pinfunction "NC3_2") (pintype "input"))
    )
    (net (code "76") (name "unconnected-(SW2-NC4-Pad4)") (class "Default")
      (node (ref "SW2") (pin "4") (pinfunction "NC4_4") (pintype "input"))
    )
    (net (code "77") (name "unconnected-(SW3-NC7-Pad1)") (class "Default")
      (node (ref "SW3") (pin "1") (pinfunction "NC7_1") (pintype "input"))
    )
    (net (code "78") (name "unconnected-(U1-P0.03_AIN1-PadB13)") (class "Default")
      (node (ref "U1") (pin "B13") (pinfunction "P0.03_AIN1_B13") (pintype "bidirectional"))
    )
    (net (code "79") (name "unconnected-(U1-P0.05_AIN3-PadK2)") (class "Default")
      (node (ref "U1") (pin "K2") (pinfunction "P0.05_AIN3_K2") (pintype "bidirectional"))
    )
    (net (code "80") (name "unconnected-(U1-P0.07_TRACECLK-PadM2)") (class "Default")
      (node (ref "U1") (pin "M2") (pinfunction "P0.07_TRACECLK_M2") (pintype "bidirectional"))
    )
    (net (code "81") (name "unconnected-(U1-P0.25-PadAC21)") (class "Default")
      (node (ref "U1") (pin "AC21") (pinfunction "P0.25_AC21") (pintype "bidirectional"))
    )
    (net (code "82") (name "unconnected-(U1-P0.27-PadH2)") (class "Default")
      (node (ref "U1") (pin "H2") (pinfunction "P0.27_H2") (pintype "bidirectional"))
    )
    (net (code "83") (name "unconnected-(U1-P0.28_AIN4-PadB11)") (class "Default")
      (node (ref "U1") (pin "B11") (pinfunction "P0.28_AIN4_B11") (pintype "bidirectional"))
    )
    (net (code "84") (name "unconnected-(U1-P0.30_AIN6-PadB9)") (class "Default")
      (node (ref "U1") (pin "B9") (pinfunction "P0.30_AIN6_B9") (pintype "bidirectional"))
    )
    (net (code "85") (name "unconnected-(U1-P1.03-PadV23)") (class "Default")
      (node (ref "U1") (pin "V23") (pinfunction "P1.03_V23") (pintype "bidirectional"))
    )
    (net (code "86") (name "unconnected-(U1-P1.05-PadT23)") (class "Default")
      (node (ref "U1") (pin "T23") (pinfunction "P1.05_T23") (pintype "bidirectional"))
    )
    (net (code "87") (name "unconnected-(U1-P1.08-PadP2)") (class "Default")
      (node (ref "U1") (pin "P2") (pinfunction "P1.08_P2") (pintype "bidirectional"))
    )
    (net (code "88") (name "unconnected-(U1-P1.12-PadB17)") (class "Default")
      (node (ref "U1") (pin "B17") (pinfunction "P1.12_B17") (pintype "bidirectional"))
    )
    (net (code "89") (name "unconnected-(U1-P1.14-PadB15)") (class "Default")
      (node (ref "U1") (pin "B15") (pinfunction "P1.14_B15") (pintype "bidirectional"))
    )
    (net (code "90") (name "unconnected-(USB1-EH-Pad6)") (class "Default")
      (node (ref "USB1") (pin "6") (pinfunction "EH_6") (pintype "input"))
    )
    (net (code "91") (name "unconnected-(USB1-NC8-Pad4)") (class "Default")
      (node (ref "USB1") (pin "4") (pinfunction "NC8_4") (pintype "input"))
    )
  )
)
